# Micro_Controller.net
KiCad netlist of a schematic drawn in Altium Designer
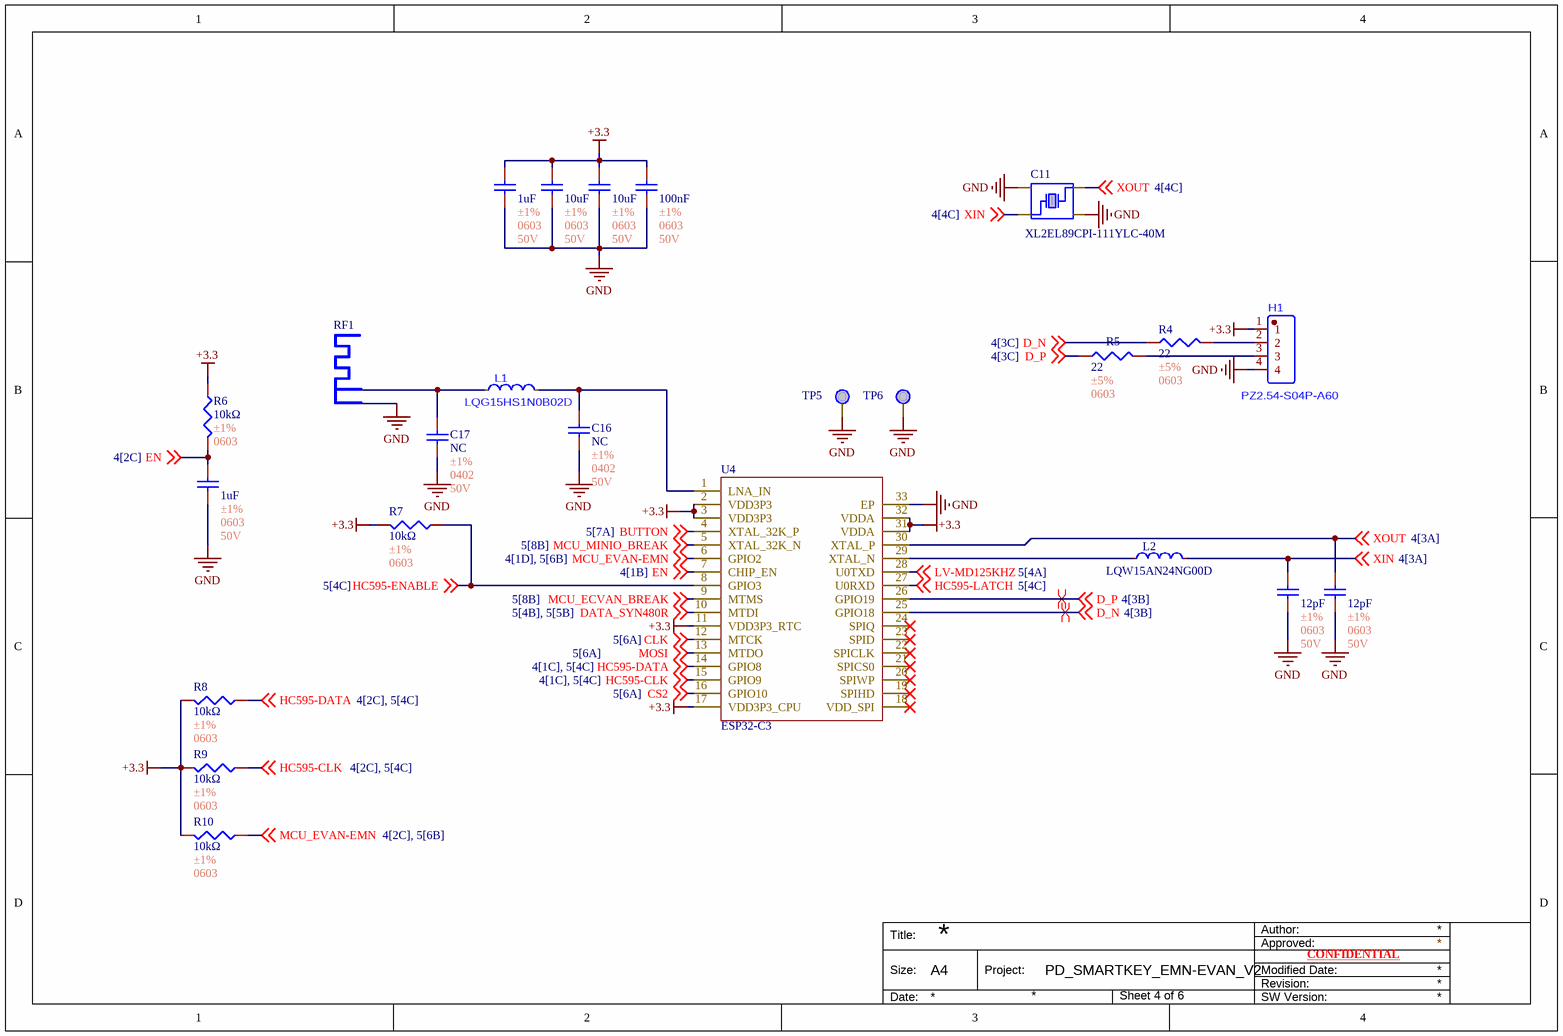
[diagram p0: Micro Controller.SchDoc]

(export (version "E")
  (design (tool "Eeschema 10.0.6"))
  (components
    (comp (ref "C11")
      (value "XL2EL89CPI-111YLC-40M")
      (footprint "XL2EL89CPI-111YLC-40M")
      (description "Crystal Oscillator 15pF SMD3225-4P Crystals RoHS")
      (fields (field (name "MANUFACTURER") "YXC Crystal Oscillators") (field (name "LCSC PART #") "C5444549"))
      (libsource (lib "Oscillator") (part "XL2EL89CPI-111YLC-40M"))
    )
    (comp (ref "C12")
      (value "1uF")
      (footprint "C0603")
      (description "50V 10pF NP0 ±1% 0402 Multilayer Ceramic Capacitors MLCC - SMD/SMT ROHS")
      (fields
        (field (name "MANUFACTURER") "YAGEO")
        (field (name "MFR. PART #") "CC0402FRNPO9BN100")
        (field (name "TOLERANCE") "±1%")
        (field (name "PACKAGE") "0603")
        (field (name "VOLTAGE RATING") "50V")
      )
      (libsource (lib "Capital") (part "C0603_1uF_±1%"))
    )
    (comp (ref "C13")
      (value "10uF")
      (footprint "C0603")
      (description "50V 10pF NP0 ±1% 0402 Multilayer Ceramic Capacitors MLCC - SMD/SMT ROHS")
      (fields
        (field (name "MANUFACTURER") "YAGEO")
        (field (name "MFR. PART #") "CC0402FRNPO9BN100")
        (field (name "TOLERANCE") "±1%")
        (field (name "PACKAGE") "0603")
        (field (name "VOLTAGE RATING") "50V")
      )
      (libsource (lib "Capital") (part "C0603_10uF_±1%"))
    )
    (comp (ref "C14")
      (value "10uF")
      (footprint "C0603")
      (description "50V 10pF NP0 ±1% 0402 Multilayer Ceramic Capacitors MLCC - SMD/SMT ROHS")
      (fields
        (field (name "MANUFACTURER") "YAGEO")
        (field (name "MFR. PART #") "CC0402FRNPO9BN100")
        (field (name "TOLERANCE") "±1%")
        (field (name "PACKAGE") "0603")
        (field (name "VOLTAGE RATING") "50V")
      )
      (libsource (lib "Capital") (part "C0603_10uF_±1%"))
    )
    (comp (ref "C15")
      (value "100nF")
      (footprint "C0603")
      (description "50V 10pF NP0 ±1% 0402 Multilayer Ceramic Capacitors MLCC - SMD/SMT ROHS")
      (fields
        (field (name "MANUFACTURER") "YAGEO")
        (field (name "MFR. PART #") "CC0402FRNPO9BN100")
        (field (name "TOLERANCE") "±1%")
        (field (name "PACKAGE") "0603")
        (field (name "VOLTAGE RATING") "50V")
      )
      (libsource (lib "Capital") (part "C0603_100nF_±1%"))
    )
    (comp (ref "C16")
      (value "NC")
      (footprint "C0402")
      (fields
        (field (name "MANUFACTURER") "YAGEO")
        (field (name "MFR. PART #") "CC0402FRNPO9BN100")
        (field (name "LCSC PART #") "C513681")
        (field (name "TOLERANCE") "±1%")
        (field (name "PACKAGE") "0402")
        (field (name "VOLTAGE RATING") "50V")
      )
      (libsource (lib "Capital") (part "C0402_NC_±1%"))
    )
    (comp (ref "C17")
      (value "NC")
      (footprint "C0402")
      (fields
        (field (name "MANUFACTURER") "YAGEO")
        (field (name "MFR. PART #") "CC0402FRNPO9BN100")
        (field (name "LCSC PART #") "C513681")
        (field (name "TOLERANCE") "±1%")
        (field (name "PACKAGE") "0402")
        (field (name "VOLTAGE RATING") "50V")
      )
      (libsource (lib "Capital") (part "C0402_NC_±1%"))
    )
    (comp (ref "C18")
      (value "1uF")
      (footprint "C0603")
      (description "50V 10pF NP0 ±1% 0402 Multilayer Ceramic Capacitors MLCC - SMD/SMT ROHS")
      (fields
        (field (name "MANUFACTURER") "YAGEO")
        (field (name "MFR. PART #") "CC0402FRNPO9BN100")
        (field (name "TOLERANCE") "±1%")
        (field (name "PACKAGE") "0603")
        (field (name "VOLTAGE RATING") "50V")
      )
      (libsource (lib "Capital") (part "C0603_1uF_±1%"))
    )
    (comp (ref "C19")
      (value "12pF")
      (footprint "C0603")
      (description "50V 10pF NP0 ±1% 0402 Multilayer Ceramic Capacitors MLCC - SMD/SMT ROHS")
      (fields
        (field (name "MANUFACTURER") "YAGEO")
        (field (name "MFR. PART #") "CC0402FRNPO9BN100")
        (field (name "TOLERANCE") "±1%")
        (field (name "PACKAGE") "0603")
        (field (name "VOLTAGE RATING") "50V")
      )
      (libsource (lib "Capital") (part "C0603_12pF_±1%"))
    )
    (comp (ref "C20")
      (value "12pF")
      (footprint "C0603")
      (description "50V 10pF NP0 ±1% 0402 Multilayer Ceramic Capacitors MLCC - SMD/SMT ROHS")
      (fields
        (field (name "MANUFACTURER") "YAGEO")
        (field (name "MFR. PART #") "CC0402FRNPO9BN100")
        (field (name "TOLERANCE") "±1%")
        (field (name "PACKAGE") "0603")
        (field (name "VOLTAGE RATING") "50V")
      )
      (libsource (lib "Capital") (part "C0603_12pF_±1%"))
    )
    (comp (ref "H1")
      (value "PZ2.54-S04P-A60")
      (footprint "J_4P_XH2.54")
      (fields (field (name "MANUFACTURER") "JXTCONN") (field (name "LCSC PART #") "C42431795"))
      (libsource (lib "Header") (part "J_4P_XH2.54"))
    )
    (comp (ref "L1")
      (value "LQG15HS1N0B02D")
      (footprint "L0402_1nH")
      (description "FIXED IND 1nH 1A 70mΩ 0402")
      (fields (field (name "MANUFACTURER") "muRata") (field (name "LCSC PART #") "C162538"))
      (libsource (lib "Inductor") (part "L0402_1nH"))
    )
    (comp (ref "L2")
      (value "LQW15AN24NG00D")
      (footprint "LQW15AN24NG00D")
      (description "FIXED IND 24nH 280mA 520mΩ 0402")
      (fields (field (name "MANUFACTURER") "muRata") (field (name "LCSC PART #") "C167472"))
      (libsource (lib "Inductor") (part "LQW15AN24NG00D"))
    )
    (comp (ref "R4")
      (value "22")
      (footprint "R0603")
      (description "100mW Thick Film Resistor 75V ±5% 0Ω 0603 Chip Resistor - Surface Mount ROHS")
      (fields
        (field (name "MANUFACTURER") "YAGEO")
        (field (name "MFR. PART #") "RC0603JR-070RL")
        (field (name "TOLERANCE") "±5%")
        (field (name "PACKAGE") "0603")
      )
      (libsource (lib "Resistor") (part "R0603_0Ω_±5%"))
    )
    (comp (ref "R5")
      (value "22")
      (footprint "R0603")
      (description "100mW Thick Film Resistor 75V ±5% 0Ω 0603 Chip Resistor - Surface Mount ROHS")
      (fields
        (field (name "MANUFACTURER") "YAGEO")
        (field (name "MFR. PART #") "RC0603JR-070RL")
        (field (name "TOLERANCE") "±5%")
        (field (name "PACKAGE") "0603")
      )
      (libsource (lib "Resistor") (part "R0603_0Ω_±5%"))
    )
    (comp (ref "R6")
      (value "10kΩ")
      (footprint "R0603")
      (description "62.5mW Thick Film Resistor 50V ±1% ±200ppm/℃ 10Ω 0402 Chip Resistor - Surface Mount ROHS")
      (fields
        (field (name "MANUFACTURER") "YAGEO")
        (field (name "MFR. PART #") "RC0402FR-0710RL")
        (field (name "TOLERANCE") "±1%")
        (field (name "PACKAGE") "0603")
      )
      (libsource (lib "Resistor") (part "R0603_10kΩ_±1%"))
    )
    (comp (ref "R7")
      (value "10kΩ")
      (footprint "R0603")
      (description "62.5mW Thick Film Resistor 50V ±1% ±200ppm/℃ 10Ω 0402 Chip Resistor - Surface Mount ROHS")
      (fields
        (field (name "MANUFACTURER") "YAGEO")
        (field (name "MFR. PART #") "RC0402FR-0710RL")
        (field (name "TOLERANCE") "±1%")
        (field (name "PACKAGE") "0603")
      )
      (libsource (lib "Resistor") (part "R0603_10kΩ_±1%"))
    )
    (comp (ref "R8")
      (value "10kΩ")
      (footprint "R0603")
      (description "62.5mW Thick Film Resistor 50V ±1% ±200ppm/℃ 10Ω 0402 Chip Resistor - Surface Mount ROHS")
      (fields
        (field (name "MANUFACTURER") "YAGEO")
        (field (name "MFR. PART #") "RC0402FR-0710RL")
        (field (name "TOLERANCE") "±1%")
        (field (name "PACKAGE") "0603")
      )
      (libsource (lib "Resistor") (part "R0603_10kΩ_±1%"))
    )
    (comp (ref "R9")
      (value "10kΩ")
      (footprint "R0603")
      (description "62.5mW Thick Film Resistor 50V ±1% ±200ppm/℃ 10Ω 0402 Chip Resistor - Surface Mount ROHS")
      (fields
        (field (name "MANUFACTURER") "YAGEO")
        (field (name "MFR. PART #") "RC0402FR-0710RL")
        (field (name "TOLERANCE") "±1%")
        (field (name "PACKAGE") "0603")
      )
      (libsource (lib "Resistor") (part "R0603_10kΩ_±1%"))
    )
    (comp (ref "R10")
      (value "10kΩ")
      (footprint "R0603")
      (description "62.5mW Thick Film Resistor 50V ±1% ±200ppm/℃ 10Ω 0402 Chip Resistor - Surface Mount ROHS")
      (fields
        (field (name "MANUFACTURER") "YAGEO")
        (field (name "MFR. PART #") "RC0402FR-0710RL")
        (field (name "TOLERANCE") "±1%")
        (field (name "PACKAGE") "0603")
      )
      (libsource (lib "Resistor") (part "R0603_10kΩ_±1%"))
    )
    (comp (ref "RF1")
      (value "~")
      (footprint "2.4GHZ-50OHMS_v1.1")
      (libsource (lib "Antenna") (part "Antenna"))
    )
    (comp (ref "TP5") (value "TP") (footprint "TP") (libsource (lib "Other") (part "TP")))
    (comp (ref "TP6") (value "TP") (footprint "TP") (libsource (lib "Other") (part "TP")))
    (comp (ref "U4")
      (value "ESP32-C3")
      (footprint "ESP32-C3")
      (description "Others 160MHz QFN-32-EP(5x5) RF Transceiver Modules and Modems RoHS")
      (fields (field (name "MANUFACTURER") "ESPRESSIF") (field (name "LCSC PART #") "C2838500"))
      (libsource (lib "MCU") (part "ESP32-C3"))
    )
  )
  (nets
    (net (code "1") (name "+3.3") (class "Default")
      (node (ref "C12") (pin "1") (pinfunction "1_1") (pintype "passive"))
      (node (ref "C13") (pin "1") (pinfunction "1_1") (pintype "passive"))
      (node (ref "C14") (pin "1") (pinfunction "1_1") (pintype "passive"))
      (node (ref "C15") (pin "1") (pinfunction "1_1") (pintype "passive"))
      (node (ref "H1") (pin "1") (pinfunction "1_1") (pintype "passive"))
      (node (ref "R10") (pin "2") (pinfunction "2_2") (pintype "passive"))
      (node (ref "R6") (pin "1") (pinfunction "1_1") (pintype "passive"))
      (node (ref "R7") (pin "2") (pinfunction "2_2") (pintype "passive"))
      (node (ref "R8") (pin "2") (pinfunction "2_2") (pintype "passive"))
      (node (ref "R9") (pin "2") (pinfunction "2_2") (pintype "passive"))
      (node (ref "U4") (pin "11") (pinfunction "VDD3P3_RTC_11") (pintype "passive"))
      (node (ref "U4") (pin "17") (pinfunction "VDD3P3_CPU_17") (pintype "passive"))
      (node (ref "U4") (pin "2") (pinfunction "VDD3P3_2") (pintype "passive"))
      (node (ref "U4") (pin "3") (pinfunction "VDD3P3_3") (pintype "passive"))
      (node (ref "U4") (pin "31") (pinfunction "VDDA_31") (pintype "passive"))
      (node (ref "U4") (pin "32") (pinfunction "VDDA_32") (pintype "passive"))
    )
    (net (code "2") (name "BUTTON") (class "Default")
      (node (ref "U4") (pin "4") (pinfunction "XTAL_32K_P_4") (pintype "passive"))
    )
    (net (code "3") (name "CLK") (class "Default")
      (node (ref "U4") (pin "12") (pinfunction "MTCK_12") (pintype "passive"))
    )
    (net (code "4") (name "CS2") (class "Default")
      (node (ref "U4") (pin "16") (pinfunction "GPIO10_16") (pintype "passive"))
    )
    (net (code "5") (name "DATA_SYN480R") (class "Default")
      (node (ref "U4") (pin "10") (pinfunction "MTDI_10") (pintype "passive"))
    )
    (net (code "6") (name "D_N") (class "Default")
      (node (ref "R4") (pin "1") (pinfunction "1_1") (pintype "passive"))
      (node (ref "U4") (pin "25") (pinfunction "GPIO18_25") (pintype "passive"))
    )
    (net (code "7") (name "D_P") (class "Default")
      (node (ref "R5") (pin "1") (pinfunction "1_1") (pintype "passive"))
      (node (ref "U4") (pin "26") (pinfunction "GPIO19_26") (pintype "passive"))
    )
    (net (code "8") (name "EN") (class "Default")
      (node (ref "C18") (pin "1") (pinfunction "1_1") (pintype "passive"))
      (node (ref "R6") (pin "2") (pinfunction "2_2") (pintype "passive"))
      (node (ref "U4") (pin "7") (pinfunction "CHIP_EN_7") (pintype "passive"))
    )
    (net (code "9") (name "GND") (class "Default")
      (node (ref "C11") (pin "2") (pinfunction "2_2") (pintype "passive"))
      (node (ref "C11") (pin "4") (pinfunction "4_4") (pintype "passive"))
      (node (ref "C12") (pin "2") (pinfunction "2_2") (pintype "passive"))
      (node (ref "C13") (pin "2") (pinfunction "2_2") (pintype "passive"))
      (node (ref "C14") (pin "2") (pinfunction "2_2") (pintype "passive"))
      (node (ref "C15") (pin "2") (pinfunction "2_2") (pintype "passive"))
      (node (ref "C16") (pin "2") (pinfunction "2_2") (pintype "passive"))
      (node (ref "C17") (pin "2") (pinfunction "2_2") (pintype "passive"))
      (node (ref "C18") (pin "2") (pinfunction "2_2") (pintype "passive"))
      (node (ref "C19") (pin "2") (pinfunction "2_2") (pintype "passive"))
      (node (ref "C20") (pin "2") (pinfunction "2_2") (pintype "passive"))
      (node (ref "H1") (pin "4") (pinfunction "4_4") (pintype "passive"))
      (node (ref "RF1") (pin "2") (pinfunction "2_2") (pintype "passive"))
      (node (ref "TP5") (pin "1") (pinfunction "1_1") (pintype "passive"))
      (node (ref "TP6") (pin "1") (pinfunction "1_1") (pintype "passive"))
      (node (ref "U4") (pin "33") (pinfunction "EP_33") (pintype "passive"))
    )
    (net (code "10") (name "HC595-CLK") (class "Default")
      (node (ref "R9") (pin "1") (pinfunction "1_1") (pintype "passive"))
      (node (ref "U4") (pin "15") (pinfunction "GPIO9_15") (pintype "passive"))
    )
    (net (code "11") (name "HC595-DATA") (class "Default")
      (node (ref "R8") (pin "1") (pinfunction "1_1") (pintype "passive"))
      (node (ref "U4") (pin "14") (pinfunction "GPIO8_14") (pintype "passive"))
    )
    (net (code "12") (name "HC595-ENABLE") (class "Default")
      (node (ref "R7") (pin "1") (pinfunction "1_1") (pintype "passive"))
      (node (ref "U4") (pin "8") (pinfunction "GPIO3_8") (pintype "passive"))
    )
    (net (code "13") (name "HC595-LATCH") (class "Default")
      (node (ref "U4") (pin "27") (pinfunction "U0RXD_27") (pintype "passive"))
    )
    (net (code "14") (name "LV-MD125KHZ") (class "Default")
      (node (ref "U4") (pin "28") (pinfunction "U0TXD_28") (pintype "passive"))
    )
    (net (code "15") (name "MCU_ECVAN_BREAK") (class "Default")
      (node (ref "U4") (pin "9") (pinfunction "MTMS_9") (pintype "passive"))
    )
    (net (code "16") (name "MCU_EVAN-EMN") (class "Default")
      (node (ref "R10") (pin "1") (pinfunction "1_1") (pintype "passive"))
      (node (ref "U4") (pin "6") (pinfunction "GPIO2_6") (pintype "passive"))
    )
    (net (code "17") (name "MCU_MINIO_BREAK") (class "Default")
      (node (ref "U4") (pin "5") (pinfunction "XTAL_32K_N_5") (pintype "passive"))
    )
    (net (code "18") (name "MOSI") (class "Default")
      (node (ref "U4") (pin "13") (pinfunction "MTDO_13") (pintype "passive"))
    )
    (net (code "19") (name "Net-(C17-Pad1)") (class "Default")
      (node (ref "C17") (pin "1") (pinfunction "1_1") (pintype "passive"))
      (node (ref "L1") (pin "1") (pinfunction "1_1") (pintype "passive"))
      (node (ref "RF1") (pin "1") (pinfunction "1_1") (pintype "passive"))
    )
    (net (code "20") (name "Net-(H1-Pad2)") (class "Default")
      (node (ref "H1") (pin "2") (pinfunction "2_2") (pintype "passive"))
      (node (ref "R4") (pin "2") (pinfunction "2_2") (pintype "passive"))
    )
    (net (code "21") (name "Net-(H1-Pad3)") (class "Default")
      (node (ref "H1") (pin "3") (pinfunction "3_3") (pintype "passive"))
      (node (ref "R5") (pin "2") (pinfunction "2_2") (pintype "passive"))
    )
    (net (code "22") (name "Net-(U4-LNA_IN)") (class "Default")
      (node (ref "C16") (pin "1") (pinfunction "1_1") (pintype "passive"))
      (node (ref "L1") (pin "2") (pinfunction "2_2") (pintype "passive"))
      (node (ref "U4") (pin "1") (pinfunction "LNA_IN_1") (pintype "passive"))
    )
    (net (code "23") (name "Net-(U4-XTAL_N)") (class "Default")
      (node (ref "L2") (pin "1") (pinfunction "1_1") (pintype "passive"))
      (node (ref "U4") (pin "29") (pinfunction "XTAL_N_29") (pintype "passive"))
    )
    (net (code "24") (name "XIN") (class "Default")
      (node (ref "C11") (pin "1") (pinfunction "1_1") (pintype "passive"))
      (node (ref "C19") (pin "1") (pinfunction "1_1") (pintype "passive"))
      (node (ref "L2") (pin "2") (pinfunction "2_2") (pintype "passive"))
    )
    (net (code "25") (name "XOUT") (class "Default")
      (node (ref "C11") (pin "3") (pinfunction "3_3") (pintype "passive"))
      (node (ref "C20") (pin "1") (pinfunction "1_1") (pintype "passive"))
      (node (ref "U4") (pin "30") (pinfunction "XTAL_P_30") (pintype "passive"))
    )
    (net (code "26") (name "unconnected-(U4-SPICLK-Pad22)") (class "Default")
      (node (ref "U4") (pin "22") (pinfunction "SPICLK_22") (pintype "passive+no_connect"))
    )
    (net (code "27") (name "unconnected-(U4-SPICS0-Pad21)") (class "Default")
      (node (ref "U4") (pin "21") (pinfunction "SPICS0_21") (pintype "passive+no_connect"))
    )
    (net (code "28") (name "unconnected-(U4-SPID-Pad23)") (class "Default")
      (node (ref "U4") (pin "23") (pinfunction "SPID_23") (pintype "passive+no_connect"))
    )
    (net (code "29") (name "unconnected-(U4-SPIHD-Pad19)") (class "Default")
      (node (ref "U4") (pin "19") (pinfunction "SPIHD_19") (pintype "passive+no_connect"))
    )
    (net (code "30") (name "unconnected-(U4-SPIQ-Pad24)") (class "Default")
      (node (ref "U4") (pin "24") (pinfunction "SPIQ_24") (pintype "passive+no_connect"))
    )
    (net (code "31") (name "unconnected-(U4-SPIWP-Pad20)") (class "Default")
      (node (ref "U4") (pin "20") (pinfunction "SPIWP_20") (pintype "passive+no_connect"))
    )
    (net (code "32") (name "unconnected-(U4-VDD_SPI-Pad18)") (class "Default")
      (node (ref "U4") (pin "18") (pinfunction "VDD_SPI_18") (pintype "passive+no_connect"))
    )
  )
)
